# Transmitter_Rev_1.net
KiCad netlist of a schematic drawn in EAGLE
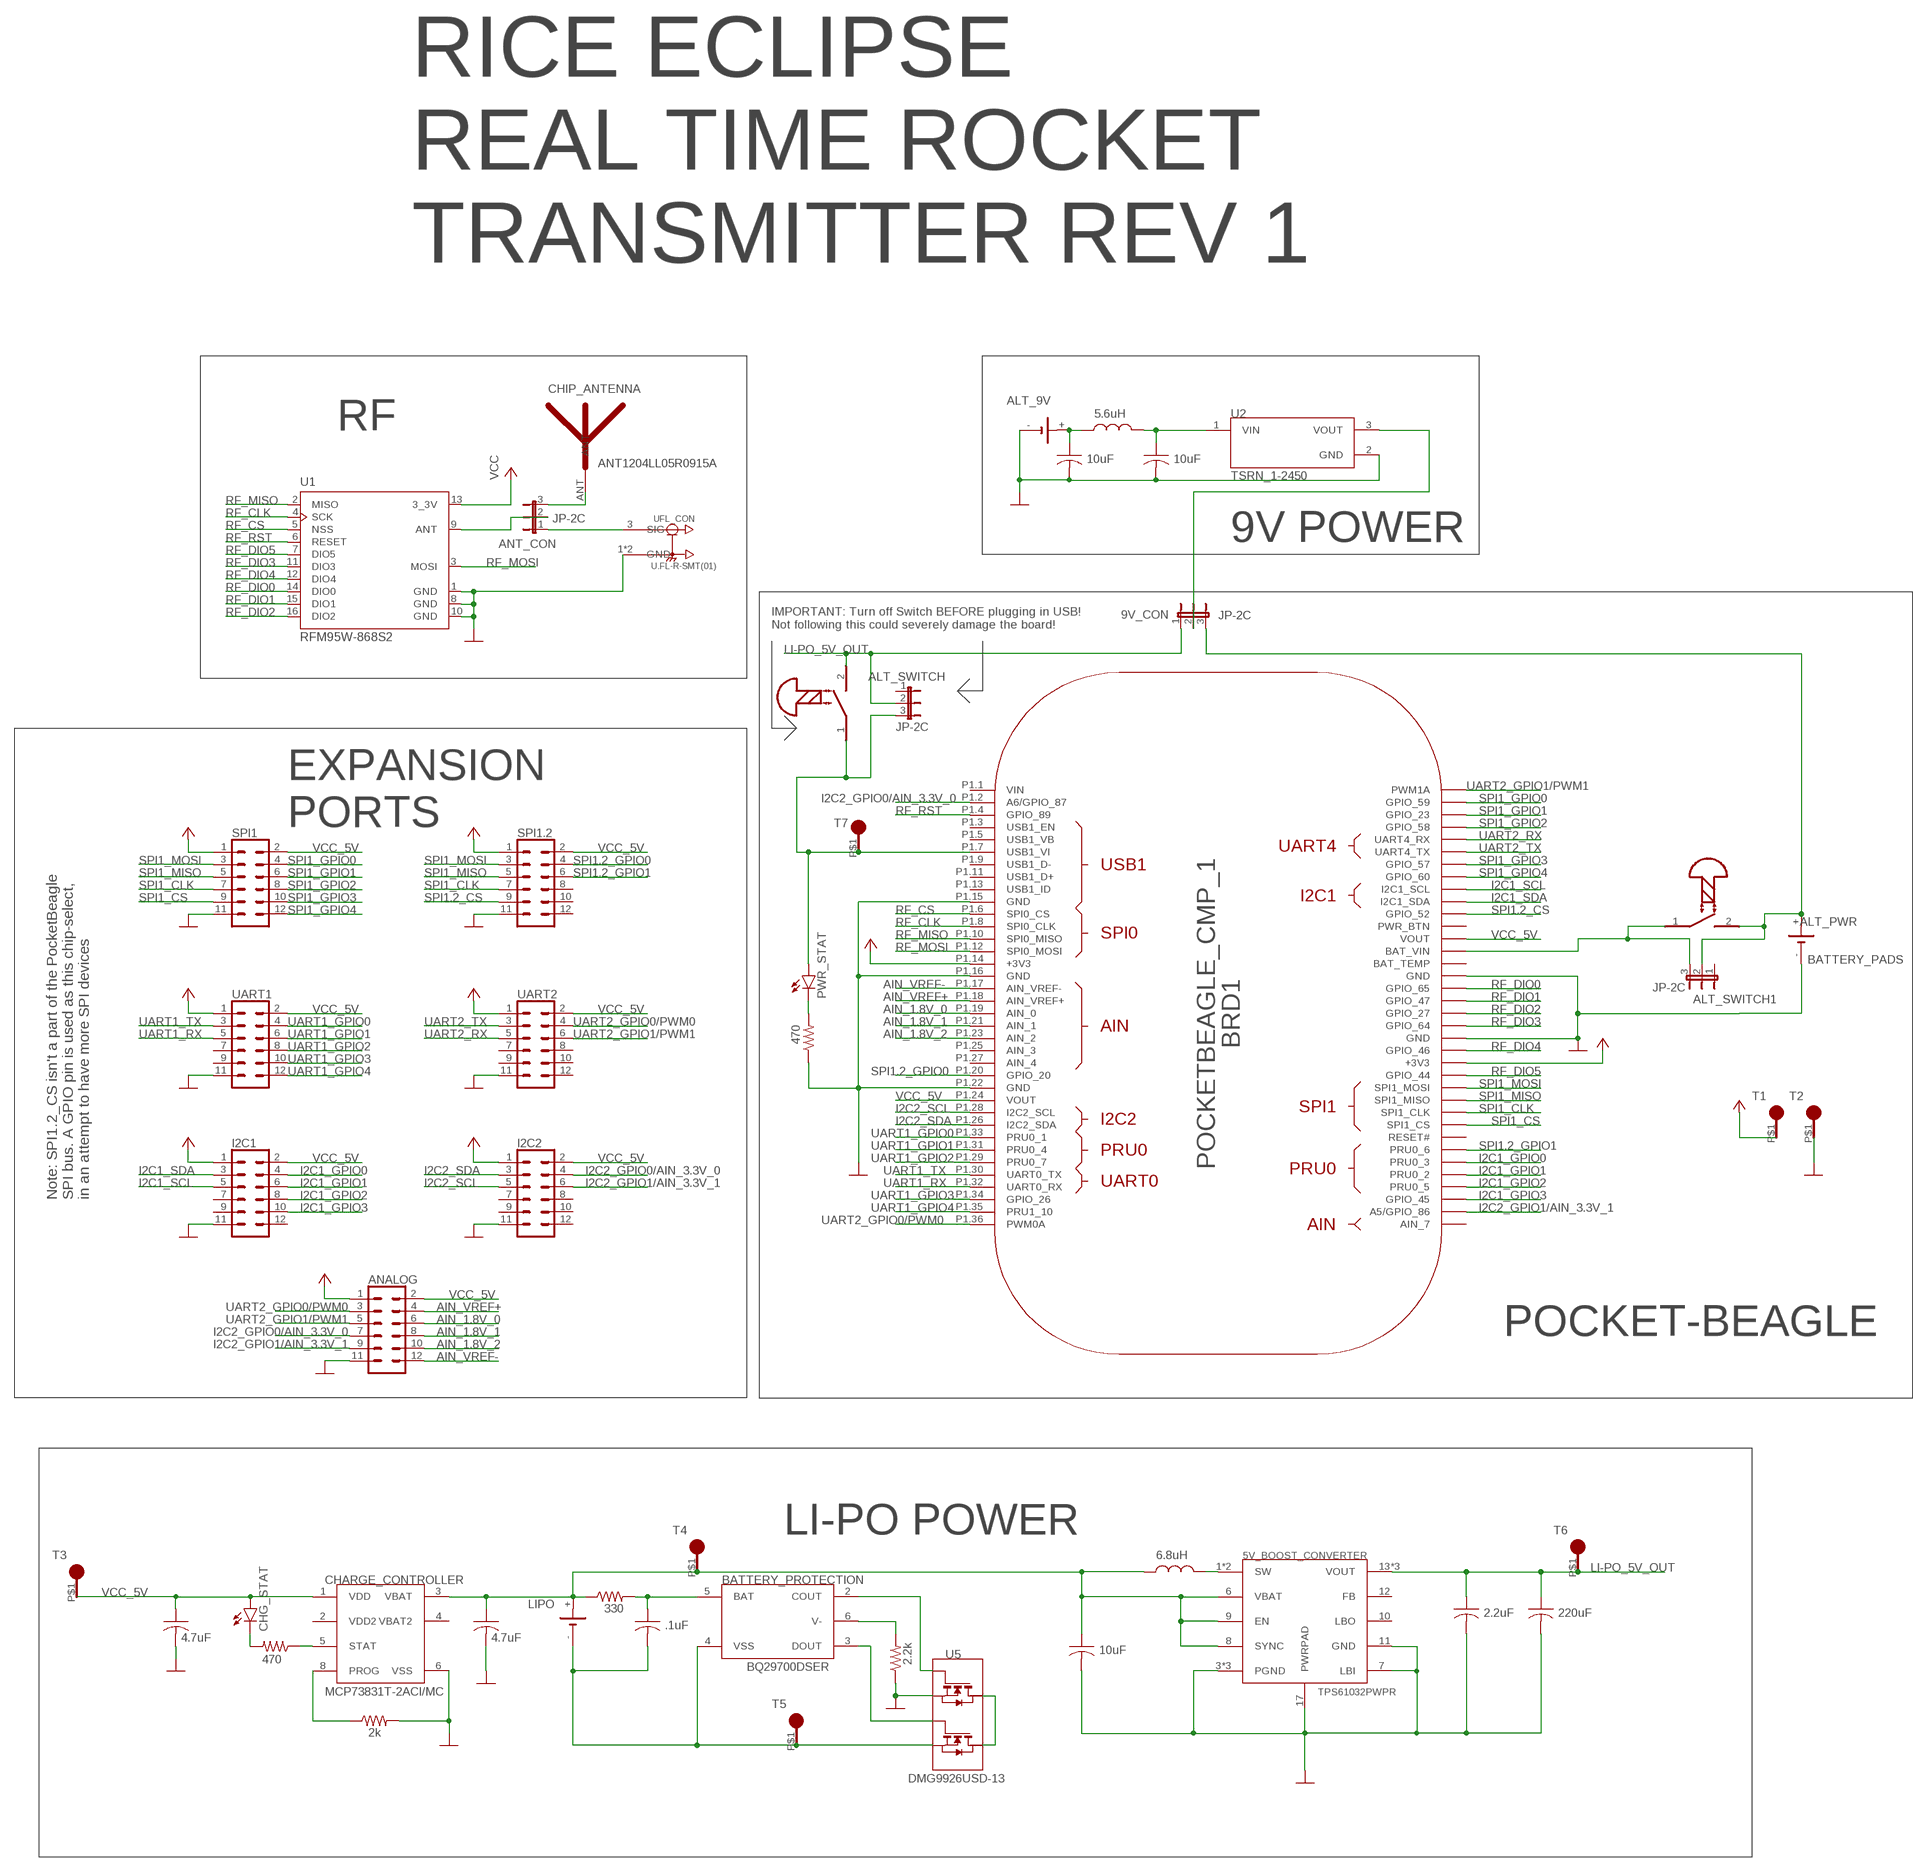
[diagram p0: schematic, sheet 1]

(export (version "E")
  (design (tool "Eeschema 10.0.6"))
  (components
    (comp (ref "5V_BOOST_CONVERTER")
      (value "TPS61032PWPR")
      (footprint "eagle-import:SOP65P640X110-17N")
      (fields (field (name "F") "TPS61032PWPR"))
      (libsource (lib "eagle-import") (part "TPS61032PWPR"))
    )
    (comp (ref "9V_C1")
      (value "10uF")
      (footprint "eagle-import:C1206")
      (libsource (lib "eagle-import") (part "C-SMD"))
    )
    (comp (ref "9V_C2")
      (value "10uF")
      (footprint "eagle-import:C1206")
      (libsource (lib "eagle-import") (part "C-SMD"))
    )
    (comp (ref "9V_CON")
      (value "JP-2C")
      (footprint "eagle-import:JP2")
      (libsource (lib "eagle-import") (part "JP-2C"))
    )
    (comp (ref "ALT_9V")
      (value "BATTERY_PADS")
      (footprint "eagle-import:POWER_PADS")
      (libsource (lib "eagle-import") (part "BATTERY_PADS"))
    )
    (comp (ref "ALT_PWR")
      (value "BATTERY_PADS")
      (footprint "eagle-import:POWER_PADS")
      (libsource (lib "eagle-import") (part "BATTERY_PADS"))
    )
    (comp (ref "ALT_SWITCH")
      (value "JP-2C")
      (footprint "eagle-import:JP2")
      (libsource (lib "eagle-import") (part "JP-2C"))
    )
    (comp (ref "ALT_SWITCH1")
      (value "JP-2C")
      (footprint "eagle-import:JP2")
      (libsource (lib "eagle-import") (part "JP-2C"))
    )
    (comp (ref "ANALOG")
      (value "2X6 FEMALE")
      (footprint "eagle-import:2X6")
      (libsource (lib "eagle-import") (part "SENSOR_BREAKOUTPTH_FEMALE"))
    )
    (comp (ref "ANT_CON")
      (value "JP-2C")
      (footprint "eagle-import:JP2")
      (libsource (lib "eagle-import") (part "JP-2C"))
    )
    (comp (ref "BATTERY_PROTECTION")
      (value "BQ29700DSER")
      (footprint "eagle-import:SON50P150X150X80-6N")
      (libsource (lib "eagle-import") (part "BQ29700DSER"))
    )
    (comp (ref "BRD1")
      (value "POCKETBEAGLE_CMP_1")
      (footprint "eagle-import:POCKETBEAGLE_CMP")
      (libsource (lib "eagle-import") (part "POCKETBEAGLE_?_1CMP"))
    )
    (comp (ref "CHARGE_CONTROLLER")
      (value "MCP73831T-2ACI/MC")
      (footprint "eagle-import:SON50P200X300X100-9N")
      (libsource (lib "eagle-import") (part "MCP73831T-2ACI/MC"))
    )
    (comp (ref "CHG_C1")
      (value "4.7uF")
      (footprint "eagle-import:C1206")
      (libsource (lib "eagle-import") (part "C-SMD"))
    )
    (comp (ref "CHG_C2")
      (value "4.7uF")
      (footprint "eagle-import:C1206")
      (libsource (lib "eagle-import") (part "C-SMD"))
    )
    (comp (ref "CHG_C3")
      (value ".1uF")
      (footprint "eagle-import:C1206")
      (libsource (lib "eagle-import") (part "C-SMD"))
    )
    (comp (ref "CHG_C4")
      (value "10uF")
      (footprint "eagle-import:C1206")
      (libsource (lib "eagle-import") (part "C-SMD"))
    )
    (comp (ref "CHG_C5")
      (value "2.2uF")
      (footprint "eagle-import:C1206")
      (libsource (lib "eagle-import") (part "C-SMD"))
    )
    (comp (ref "CHG_C6")
      (value "220uF")
      (footprint "eagle-import:C1206")
      (libsource (lib "eagle-import") (part "C-SMD"))
    )
    (comp (ref "CHG_R1")
      (value "2k")
      (footprint "eagle-import:RES_SMW52R0JT")
      (libsource (lib "eagle-import") (part "R-SMD"))
    )
    (comp (ref "CHG_R2")
      (value "470")
      (footprint "eagle-import:RES_SMW52R0JT")
      (libsource (lib "eagle-import") (part "R-SMD"))
    )
    (comp (ref "CHG_R3")
      (value "330")
      (footprint "eagle-import:RES_SMW52R0JT")
      (libsource (lib "eagle-import") (part "R-SMD"))
    )
    (comp (ref "CHG_R4")
      (value "2.2k")
      (footprint "eagle-import:RES_SMW52R0JT")
      (libsource (lib "eagle-import") (part "R-SMD"))
    )
    (comp (ref "CHG_R5")
      (value "470")
      (footprint "eagle-import:RES_SMW52R0JT")
      (libsource (lib "eagle-import") (part "R-SMD"))
    )
    (comp (ref "CHG_STAT")
      (value "LED5MM")
      (footprint "eagle-import:LED5MM")
      (libsource (lib "eagle-import") (part "LED5MM"))
    )
    (comp (ref "CHIP_ANTENNA")
      (value "ANT1204LL05R0915A")
      (footprint "eagle-import:SMD_ANTENNA")
      (libsource (lib "eagle-import") (part "ANT1204LL05R0915A"))
    )
    (comp (ref "I2C1")
      (value "2X6 FEMALE")
      (footprint "eagle-import:2X6")
      (libsource (lib "eagle-import") (part "SENSOR_BREAKOUTPTH_FEMALE"))
    )
    (comp (ref "I2C2")
      (value "2X6 FEMALE")
      (footprint "eagle-import:2X6")
      (libsource (lib "eagle-import") (part "SENSOR_BREAKOUTPTH_FEMALE"))
    )
    (comp (ref "L1")
      (value "5.6uH")
      (footprint "eagle-import:L-DS75LC")
      (libsource (lib "eagle-import") (part "L_SMD"))
    )
    (comp (ref "L2")
      (value "6.8uH")
      (footprint "eagle-import:L-DS75LC")
      (libsource (lib "eagle-import") (part "L_SMD"))
    )
    (comp (ref "LIPO")
      (value "BATTERY_PADS")
      (footprint "eagle-import:POWER_PADS")
      (libsource (lib "eagle-import") (part "BATTERY_PADS"))
    )
    (comp (ref "PWR_STAT")
      (value "LED5MM")
      (footprint "eagle-import:LED5MM")
      (libsource (lib "eagle-import") (part "LED5MM"))
    )
    (comp (ref "SPI1")
      (value "SNSR_BRKOUT")
      (footprint "eagle-import:2X6")
      (libsource (lib "eagle-import") (part "SENSOR_BREAKOUTPTH_FEMALE"))
    )
    (comp (ref "SPI1.2")
      (value "2X6 FEMALE")
      (footprint "eagle-import:2X6")
      (libsource (lib "eagle-import") (part "SENSOR_BREAKOUTPTH_FEMALE"))
    )
    (comp (ref "SW1")
      (value "SCREW_SWITCH")
      (footprint "eagle-import:SCREW_SWITCH")
      (libsource (lib "eagle-import") (part "SCREW_SWITCH"))
    )
    (comp (ref "SW2")
      (value "SCREW_SWITCH")
      (footprint "eagle-import:SCREW_SWITCH")
      (libsource (lib "eagle-import") (part "SCREW_SWITCH"))
    )
    (comp (ref "T1")
      (value "TEST_PAD")
      (footprint "eagle-import:TEST_PAD")
      (libsource (lib "eagle-import") (part "TEST_PAD"))
    )
    (comp (ref "T2")
      (value "TEST_PAD")
      (footprint "eagle-import:TEST_PAD")
      (libsource (lib "eagle-import") (part "TEST_PAD"))
    )
    (comp (ref "T3")
      (value "TEST_PAD")
      (footprint "eagle-import:TEST_PAD")
      (libsource (lib "eagle-import") (part "TEST_PAD"))
    )
    (comp (ref "T4")
      (value "TEST_PAD")
      (footprint "eagle-import:TEST_PAD")
      (libsource (lib "eagle-import") (part "TEST_PAD"))
    )
    (comp (ref "T5")
      (value "TEST_PAD")
      (footprint "eagle-import:TEST_PAD")
      (libsource (lib "eagle-import") (part "TEST_PAD"))
    )
    (comp (ref "T6")
      (value "TEST_PAD")
      (footprint "eagle-import:TEST_PAD")
      (libsource (lib "eagle-import") (part "TEST_PAD"))
    )
    (comp (ref "T7")
      (value "TEST_PAD")
      (footprint "eagle-import:TEST_PAD")
      (libsource (lib "eagle-import") (part "TEST_PAD"))
    )
    (comp (ref "U1")
      (value "RFM95W-868S2")
      (footprint "eagle-import:XCVR_RFM95W-868S2")
      (fields (field (name "MF") "RF"))
      (libsource (lib "eagle-import") (part "RFM95W-868S2"))
    )
    (comp (ref "U2")
      (value "TSRN_1-2450")
      (footprint "eagle-import:CONV_TSRN_1-2433")
      (fields (field (name "MF") "Traco Power") (field (name "MP") "TSRN 1-2450"))
      (libsource (lib "eagle-import") (part "TSRN_1-2450"))
    )
    (comp (ref "U5")
      (value "DMG9926USD-13")
      (footprint "eagle-import:SOIC127P600X175-8N")
      (libsource (lib "eagle-import") (part "DMG9926USD-13"))
    )
    (comp (ref "UART1")
      (value "2X6 FEMALE")
      (footprint "eagle-import:2X6")
      (libsource (lib "eagle-import") (part "SENSOR_BREAKOUTPTH_FEMALE"))
    )
    (comp (ref "UART2")
      (value "2X6 FEMALE")
      (footprint "eagle-import:2X6")
      (libsource (lib "eagle-import") (part "SENSOR_BREAKOUTPTH_FEMALE"))
    )
    (comp (ref "UFL_CON")
      (value "U.FL-R-SMT(01)")
      (footprint "eagle-import:HRS_U.FL-R-SMT(01)")
      (fields
        (field (name "DIGI-KEY_PART_NUMBER") "H9161-ND")
        (field (name "MF") "Hirose")
        (field (name "MP") "U.FL-R-SMT_01_")
      )
      (libsource (lib "eagle-import") (part "U.FL-R-SMT(01)"))
    )
  )
  (nets
    (net (code "1") (name "/AIN_1.8V_0") (class "Default")
      (node (ref "ANALOG") (pin "6") (pinfunction "6_6") (pintype "passive"))
      (node (ref "BRD1") (pin "P1.19") (pinfunction "AIN_0_P1.19") (pintype "bidirectional"))
    )
    (net (code "2") (name "/AIN_1.8V_1") (class "Default")
      (node (ref "ANALOG") (pin "8") (pinfunction "8_8") (pintype "passive"))
      (node (ref "BRD1") (pin "P1.21") (pinfunction "AIN_1_P1.21") (pintype "bidirectional"))
    )
    (net (code "3") (name "/AIN_1.8V_2") (class "Default")
      (node (ref "ANALOG") (pin "10") (pinfunction "10_10") (pintype "passive"))
      (node (ref "BRD1") (pin "P1.23") (pinfunction "AIN_2_P1.23") (pintype "bidirectional"))
    )
    (net (code "4") (name "/AIN_VREF+") (class "Default")
      (node (ref "ANALOG") (pin "4") (pinfunction "4_4") (pintype "passive"))
      (node (ref "BRD1") (pin "P1.18") (pinfunction "AIN_VREF+_P1.18") (pintype "bidirectional"))
    )
    (net (code "5") (name "/AIN_VREF-") (class "Default")
      (node (ref "ANALOG") (pin "12") (pinfunction "12_12") (pintype "passive"))
      (node (ref "BRD1") (pin "P1.17") (pinfunction "AIN_VREF-_P1.17") (pintype "bidirectional"))
    )
    (net (code "6") (name "/I2C1_GPIO0") (class "Default")
      (node (ref "BRD1") (pin "P2.30") (pinfunction "PRU0_3_P2.30") (pintype "bidirectional"))
      (node (ref "I2C1") (pin "4") (pinfunction "4_4") (pintype "passive"))
    )
    (net (code "7") (name "/I2C1_GPIO1") (class "Default")
      (node (ref "BRD1") (pin "P2.32") (pinfunction "PRU0_2_P2.32") (pintype "bidirectional"))
      (node (ref "I2C1") (pin "6") (pinfunction "6_6") (pintype "passive"))
    )
    (net (code "8") (name "/I2C1_GPIO2") (class "Default")
      (node (ref "BRD1") (pin "P2.34") (pinfunction "PRU0_5_P2.34") (pintype "bidirectional"))
      (node (ref "I2C1") (pin "8") (pinfunction "8_8") (pintype "passive"))
    )
    (net (code "9") (name "/I2C1_GPIO3") (class "Default")
      (node (ref "BRD1") (pin "P2.33") (pinfunction "GPIO_45_P2.33") (pintype "bidirectional"))
      (node (ref "I2C1") (pin "10") (pinfunction "10_10") (pintype "passive"))
    )
    (net (code "10") (name "/I2C1_SCL") (class "Default")
      (node (ref "BRD1") (pin "P2.9") (pinfunction "I2C1_SCL_P2.9") (pintype "bidirectional"))
      (node (ref "I2C1") (pin "5") (pinfunction "5_5") (pintype "passive"))
    )
    (net (code "11") (name "/I2C1_SDA") (class "Default")
      (node (ref "BRD1") (pin "P2.11") (pinfunction "I2C1_SDA_P2.11") (pintype "bidirectional"))
      (node (ref "I2C1") (pin "3") (pinfunction "3_3") (pintype "passive"))
    )
    (net (code "12") (name "/I2C2_GPIO0{slash}AIN_3.3V_0") (class "Default")
      (node (ref "ANALOG") (pin "7") (pinfunction "7_7") (pintype "passive"))
      (node (ref "BRD1") (pin "P1.2") (pinfunction "A6/GPIO_87_P1.2") (pintype "bidirectional"))
      (node (ref "I2C2") (pin "4") (pinfunction "4_4") (pintype "passive"))
    )
    (net (code "13") (name "/I2C2_GPIO1{slash}AIN_3.3V_1") (class "Default")
      (node (ref "ANALOG") (pin "9") (pinfunction "9_9") (pintype "passive"))
      (node (ref "BRD1") (pin "P2.35") (pinfunction "A5/GPIO_86_P2.35") (pintype "bidirectional"))
      (node (ref "I2C2") (pin "6") (pinfunction "6_6") (pintype "passive"))
    )
    (net (code "14") (name "/I2C2_SCL") (class "Default")
      (node (ref "BRD1") (pin "P1.28") (pinfunction "I2C2_SCL_P1.28") (pintype "bidirectional"))
      (node (ref "I2C2") (pin "5") (pinfunction "5_5") (pintype "passive"))
    )
    (net (code "15") (name "/I2C2_SDA") (class "Default")
      (node (ref "BRD1") (pin "P1.26") (pinfunction "I2C2_SDA_P1.26") (pintype "bidirectional"))
      (node (ref "I2C2") (pin "3") (pinfunction "3_3") (pintype "passive"))
    )
    (net (code "16") (name "/LI-PO_5V_OUT") (class "Default")
      (node (ref "5V_BOOST_CONVERTER") (pin "13") (pinfunction "VOUT_13") (pintype "bidirectional"))
      (node (ref "5V_BOOST_CONVERTER") (pin "14") (pinfunction "VOUT_14") (pintype "bidirectional"))
      (node (ref "5V_BOOST_CONVERTER") (pin "15") (pinfunction "VOUT_15") (pintype "bidirectional"))
      (node (ref "9V_CON") (pin "1") (pinfunction "1_1") (pintype "passive"))
      (node (ref "ALT_SWITCH") (pin "2") (pinfunction "2_2") (pintype "passive"))
      (node (ref "CHG_C5") (pin "1") (pinfunction "1_1") (pintype "passive"))
      (node (ref "CHG_C6") (pin "1") (pinfunction "1_1") (pintype "passive"))
      (node (ref "SW1") (pin "2") (pinfunction "2_2") (pintype "passive"))
      (node (ref "T6") (pin "P$1") (pinfunction "P$1_P$1") (pintype "passive"))
    )
    (net (code "17") (name "/RF_CLK") (class "Default")
      (node (ref "BRD1") (pin "P1.8") (pinfunction "SPI0_CLK_P1.8") (pintype "bidirectional"))
      (node (ref "U1") (pin "4") (pinfunction "SCK_4") (pintype "input"))
    )
    (net (code "18") (name "/RF_CS") (class "Default")
      (node (ref "BRD1") (pin "P1.6") (pinfunction "SPI0_CS_P1.6") (pintype "bidirectional"))
      (node (ref "U1") (pin "5") (pinfunction "NSS_5") (pintype "input"))
    )
    (net (code "19") (name "/RF_DIO0") (class "Default")
      (node (ref "BRD1") (pin "P2.17") (pinfunction "GPIO_65_P2.17") (pintype "bidirectional"))
      (node (ref "U1") (pin "14") (pinfunction "DIO0_14") (pintype "bidirectional"))
    )
    (net (code "20") (name "/RF_DIO1") (class "Default")
      (node (ref "BRD1") (pin "P2.18") (pinfunction "GPIO_47_P2.18") (pintype "bidirectional"))
      (node (ref "U1") (pin "15") (pinfunction "DIO1_15") (pintype "bidirectional"))
    )
    (net (code "21") (name "/RF_DIO2") (class "Default")
      (node (ref "BRD1") (pin "P2.19") (pinfunction "GPIO_27_P2.19") (pintype "bidirectional"))
      (node (ref "U1") (pin "16") (pinfunction "DIO2_16") (pintype "bidirectional"))
    )
    (net (code "22") (name "/RF_DIO3") (class "Default")
      (node (ref "BRD1") (pin "P2.20") (pinfunction "GPIO_64_P2.20") (pintype "bidirectional"))
      (node (ref "U1") (pin "11") (pinfunction "DIO3_11") (pintype "bidirectional"))
    )
    (net (code "23") (name "/RF_DIO4") (class "Default")
      (node (ref "BRD1") (pin "P2.22") (pinfunction "GPIO_46_P2.22") (pintype "bidirectional"))
      (node (ref "U1") (pin "12") (pinfunction "DIO4_12") (pintype "bidirectional"))
    )
    (net (code "24") (name "/RF_DIO5") (class "Default")
      (node (ref "BRD1") (pin "P2.24") (pinfunction "GPIO_44_P2.24") (pintype "bidirectional"))
      (node (ref "U1") (pin "7") (pinfunction "DIO5_7") (pintype "bidirectional"))
    )
    (net (code "25") (name "/RF_MISO") (class "Default")
      (node (ref "BRD1") (pin "P1.10") (pinfunction "SPI0_MISO_P1.10") (pintype "bidirectional"))
      (node (ref "U1") (pin "2") (pinfunction "MISO_2") (pintype "input"))
    )
    (net (code "26") (name "/RF_MOSI") (class "Default")
      (node (ref "BRD1") (pin "P1.12") (pinfunction "SPI0_MOSI_P1.12") (pintype "bidirectional"))
      (node (ref "U1") (pin "3") (pinfunction "MOSI_3") (pintype "output"))
    )
    (net (code "27") (name "/RF_RST") (class "Default")
      (node (ref "BRD1") (pin "P1.4") (pinfunction "GPIO_89_P1.4") (pintype "bidirectional"))
      (node (ref "U1") (pin "6") (pinfunction "RESET_6") (pintype "bidirectional"))
    )
    (net (code "28") (name "/SPI1.2_CS") (class "Default")
      (node (ref "BRD1") (pin "P2.10") (pinfunction "GPIO_52_P2.10") (pintype "bidirectional"))
      (node (ref "SPI1.2") (pin "9") (pinfunction "9_9") (pintype "passive"))
    )
    (net (code "29") (name "/SPI1.2_GPIO0") (class "Default")
      (node (ref "BRD1") (pin "P1.20") (pinfunction "GPIO_20_P1.20") (pintype "bidirectional"))
      (node (ref "SPI1.2") (pin "4") (pinfunction "4_4") (pintype "passive"))
    )
    (net (code "30") (name "/SPI1.2_GPIO1") (class "Default")
      (node (ref "BRD1") (pin "P2.28") (pinfunction "PRU0_6_P2.28") (pintype "bidirectional"))
      (node (ref "SPI1.2") (pin "6") (pinfunction "6_6") (pintype "passive"))
    )
    (net (code "31") (name "/SPI1_CLK") (class "Default")
      (node (ref "BRD1") (pin "P2.29") (pinfunction "SPI1_CLK_P2.29") (pintype "bidirectional"))
      (node (ref "SPI1") (pin "7") (pinfunction "7_7") (pintype "passive"))
      (node (ref "SPI1.2") (pin "7") (pinfunction "7_7") (pintype "passive"))
    )
    (net (code "32") (name "/SPI1_CS") (class "Default")
      (node (ref "BRD1") (pin "P2.31") (pinfunction "SPI1_CS_P2.31") (pintype "bidirectional"))
      (node (ref "SPI1") (pin "9") (pinfunction "9_9") (pintype "passive"))
    )
    (net (code "33") (name "/SPI1_GPIO0") (class "Default")
      (node (ref "BRD1") (pin "P2.2") (pinfunction "GPIO_59_P2.2") (pintype "bidirectional"))
      (node (ref "SPI1") (pin "4") (pinfunction "4_4") (pintype "passive"))
    )
    (net (code "34") (name "/SPI1_GPIO1") (class "Default")
      (node (ref "BRD1") (pin "P2.3") (pinfunction "GPIO_23_P2.3") (pintype "bidirectional"))
      (node (ref "SPI1") (pin "6") (pinfunction "6_6") (pintype "passive"))
    )
    (net (code "35") (name "/SPI1_GPIO2") (class "Default")
      (node (ref "BRD1") (pin "P2.4") (pinfunction "GPIO_58_P2.4") (pintype "bidirectional"))
      (node (ref "SPI1") (pin "8") (pinfunction "8_8") (pintype "passive"))
    )
    (net (code "36") (name "/SPI1_GPIO3") (class "Default")
      (node (ref "BRD1") (pin "P2.6") (pinfunction "GPIO_57_P2.6") (pintype "bidirectional"))
      (node (ref "SPI1") (pin "10") (pinfunction "10_10") (pintype "passive"))
    )
    (net (code "37") (name "/SPI1_GPIO4") (class "Default")
      (node (ref "BRD1") (pin "P2.8") (pinfunction "GPIO_60_P2.8") (pintype "bidirectional"))
      (node (ref "SPI1") (pin "12") (pinfunction "12_12") (pintype "passive"))
    )
    (net (code "38") (name "/SPI1_MISO") (class "Default")
      (node (ref "BRD1") (pin "P2.27") (pinfunction "SPI1_MISO_P2.27") (pintype "bidirectional"))
      (node (ref "SPI1") (pin "5") (pinfunction "5_5") (pintype "passive"))
      (node (ref "SPI1.2") (pin "5") (pinfunction "5_5") (pintype "passive"))
    )
    (net (code "39") (name "/SPI1_MOSI") (class "Default")
      (node (ref "BRD1") (pin "P2.25") (pinfunction "SPI1_MOSI_P2.25") (pintype "bidirectional"))
      (node (ref "SPI1") (pin "3") (pinfunction "3_3") (pintype "passive"))
      (node (ref "SPI1.2") (pin "3") (pinfunction "3_3") (pintype "passive"))
    )
    (net (code "40") (name "/UART1_GPIO0") (class "Default")
      (node (ref "BRD1") (pin "P1.33") (pinfunction "PRU0_1_P1.33") (pintype "bidirectional"))
      (node (ref "UART1") (pin "4") (pinfunction "4_4") (pintype "passive"))
    )
    (net (code "41") (name "/UART1_GPIO1") (class "Default")
      (node (ref "BRD1") (pin "P1.31") (pinfunction "PRU0_4_P1.31") (pintype "bidirectional"))
      (node (ref "UART1") (pin "6") (pinfunction "6_6") (pintype "passive"))
    )
    (net (code "42") (name "/UART1_GPIO2") (class "Default")
      (node (ref "BRD1") (pin "P1.29") (pinfunction "PRU0_7_P1.29") (pintype "bidirectional"))
      (node (ref "UART1") (pin "8") (pinfunction "8_8") (pintype "passive"))
    )
    (net (code "43") (name "/UART1_GPIO3") (class "Default")
      (node (ref "BRD1") (pin "P1.34") (pinfunction "GPIO_26_P1.34") (pintype "bidirectional"))
      (node (ref "UART1") (pin "10") (pinfunction "10_10") (pintype "passive"))
    )
    (net (code "44") (name "/UART1_GPIO4") (class "Default")
      (node (ref "BRD1") (pin "P1.35") (pinfunction "PRU1_10_P1.35") (pintype "bidirectional"))
      (node (ref "UART1") (pin "12") (pinfunction "12_12") (pintype "passive"))
    )
    (net (code "45") (name "/UART1_RX") (class "Default")
      (node (ref "BRD1") (pin "P1.32") (pinfunction "UART0_RX_P1.32") (pintype "bidirectional"))
      (node (ref "UART1") (pin "5") (pinfunction "5_5") (pintype "passive"))
    )
    (net (code "46") (name "/UART1_TX") (class "Default")
      (node (ref "BRD1") (pin "P1.30") (pinfunction "UART0_TX_P1.30") (pintype "bidirectional"))
      (node (ref "UART1") (pin "3") (pinfunction "3_3") (pintype "passive"))
    )
    (net (code "47") (name "/UART2_GPIO0{slash}PWM0") (class "Default")
      (node (ref "ANALOG") (pin "3") (pinfunction "3_3") (pintype "passive"))
      (node (ref "BRD1") (pin "P1.36") (pinfunction "PWM0A_P1.36") (pintype "bidirectional"))
      (node (ref "UART2") (pin "4") (pinfunction "4_4") (pintype "passive"))
    )
    (net (code "48") (name "/UART2_GPIO1{slash}PWM1") (class "Default")
      (node (ref "ANALOG") (pin "5") (pinfunction "5_5") (pintype "passive"))
      (node (ref "BRD1") (pin "P2.1") (pinfunction "PWM1A_P2.1") (pintype "bidirectional"))
      (node (ref "UART2") (pin "6") (pinfunction "6_6") (pintype "passive"))
    )
    (net (code "49") (name "/UART2_RX") (class "Default")
      (node (ref "BRD1") (pin "P2.5") (pinfunction "UART4_RX_P2.5") (pintype "bidirectional"))
      (node (ref "UART2") (pin "5") (pinfunction "5_5") (pintype "passive"))
    )
    (net (code "50") (name "/UART2_TX") (class "Default")
      (node (ref "BRD1") (pin "P2.7") (pinfunction "UART4_TX_P2.7") (pintype "bidirectional"))
      (node (ref "UART2") (pin "3") (pinfunction "3_3") (pintype "passive"))
    )
    (net (code "51") (name "/VCC_5V") (class "Default")
      (node (ref "ANALOG") (pin "2") (pinfunction "2_2") (pintype "passive"))
      (node (ref "BRD1") (pin "P1.24") (pinfunction "VOUT_P1.24") (pintype "bidirectional"))
      (node (ref "BRD1") (pin "P2.13") (pinfunction "VOUT_P2.13") (pintype "bidirectional"))
      (node (ref "CHARGE_CONTROLLER") (pin "1") (pinfunction "VDD_1") (pintype "bidirectional"))
      (node (ref "CHG_C1") (pin "1") (pinfunction "1_1") (pintype "passive"))
      (node (ref "CHG_STAT") (pin "A") (pinfunction "A_A") (pintype "passive"))
      (node (ref "I2C1") (pin "2") (pinfunction "2_2") (pintype "passive"))
      (node (ref "I2C2") (pin "2") (pinfunction "2_2") (pintype "passive"))
      (node (ref "SPI1") (pin "2") (pinfunction "2_2") (pintype "passive"))
      (node (ref "SPI1.2") (pin "2") (pinfunction "2_2") (pintype "passive"))
      (node (ref "T3") (pin "P$1") (pinfunction "P$1_P$1") (pintype "passive"))
      (node (ref "UART1") (pin "2") (pinfunction "2_2") (pintype "passive"))
      (node (ref "UART2") (pin "2") (pinfunction "2_2") (pintype "passive"))
    )
    (net (code "52") (name "GND") (class "Default")
      (node (ref "5V_BOOST_CONVERTER") (pin "11") (pinfunction "GND_11") (pintype "bidirectional"))
      (node (ref "5V_BOOST_CONVERTER") (pin "17") (pinfunction "PWRPAD_17") (pintype "bidirectional"))
      (node (ref "5V_BOOST_CONVERTER") (pin "3") (pinfunction "PGND_3") (pintype "bidirectional"))
      (node (ref "5V_BOOST_CONVERTER") (pin "4") (pinfunction "PGND_4") (pintype "bidirectional"))
      (node (ref "5V_BOOST_CONVERTER") (pin "5") (pinfunction "PGND_5") (pintype "bidirectional"))
      (node (ref "5V_BOOST_CONVERTER") (pin "7") (pinfunction "LBI_7") (pintype "bidirectional"))
      (node (ref "9V_C1") (pin "2") (pinfunction "2_2") (pintype "passive"))
      (node (ref "9V_C2") (pin "2") (pinfunction "2_2") (pintype "passive"))
      (node (ref "ALT_9V") (pin "-") (pinfunction "-_-") (pintype "passive"))
      (node (ref "ALT_PWR") (pin "-") (pinfunction "-_-") (pintype "passive"))
      (node (ref "ANALOG") (pin "11") (pinfunction "11_11") (pintype "passive"))
      (node (ref "BRD1") (pin "P1.15") (pinfunction "GND_P1.15") (pintype "bidirectional"))
      (node (ref "BRD1") (pin "P1.16") (pinfunction "GND_P1.16") (pintype "bidirectional"))
      (node (ref "BRD1") (pin "P1.22") (pinfunction "GND_P1.22") (pintype "bidirectional"))
      (node (ref "BRD1") (pin "P2.15") (pinfunction "GND_P2.15") (pintype "bidirectional"))
      (node (ref "BRD1") (pin "P2.21") (pinfunction "GND_P2.21") (pintype "bidirectional"))
      (node (ref "CHARGE_CONTROLLER") (pin "6") (pinfunction "VSS_6") (pintype "bidirectional"))
      (node (ref "CHG_C1") (pin "2") (pinfunction "2_2") (pintype "passive"))
      (node (ref "CHG_C2") (pin "2") (pinfunction "2_2") (pintype "passive"))
      (node (ref "CHG_C4") (pin "2") (pinfunction "2_2") (pintype "passive"))
      (node (ref "CHG_C5") (pin "2") (pinfunction "2_2") (pintype "passive"))
      (node (ref "CHG_C6") (pin "2") (pinfunction "2_2") (pintype "passive"))
      (node (ref "CHG_R1") (pin "2") (pinfunction "2_2") (pintype "passive"))
      (node (ref "CHG_R4") (pin "1") (pinfunction "1_1") (pintype "passive"))
      (node (ref "CHG_R5") (pin "1") (pinfunction "1_1") (pintype "passive"))
      (node (ref "I2C1") (pin "11") (pinfunction "11_11") (pintype "passive"))
      (node (ref "I2C2") (pin "11") (pinfunction "11_11") (pintype "passive"))
      (node (ref "SPI1") (pin "11") (pinfunction "11_11") (pintype "passive"))
      (node (ref "SPI1.2") (pin "11") (pinfunction "11_11") (pintype "passive"))
      (node (ref "T2") (pin "P$1") (pinfunction "P$1_P$1") (pintype "passive"))
      (node (ref "U1") (pin "1") (pinfunction "GND_1") (pintype "power_in"))
      (node (ref "U1") (pin "10") (pinfunction "GND_10") (pintype "power_in"))
      (node (ref "U1") (pin "8") (pinfunction "GND_8") (pintype "power_in"))
      (node (ref "U2") (pin "2") (pinfunction "GND_2") (pintype "power_in"))
      (node (ref "U5") (pin "1") (pinfunction "S1_1") (pintype "passive"))
      (node (ref "UART1") (pin "11") (pinfunction "11_11") (pintype "passive"))
      (node (ref "UART2") (pin "11") (pinfunction "11_11") (pintype "passive"))
      (node (ref "UFL_CON") (pin "1") (pinfunction "GND_1") (pintype "passive"))
      (node (ref "UFL_CON") (pin "2") (pinfunction "GND_2") (pintype "passive"))
    )
    (net (code "53") (name "Net-(5V_BOOST_CONVERTER-EN)") (class "Default")
      (node (ref "5V_BOOST_CONVERTER") (pin "6") (pinfunction "VBAT_6") (pintype "bidirectional"))
      (node (ref "5V_BOOST_CONVERTER") (pin "8") (pinfunction "SYNC_8") (pintype "bidirectional"))
      (node (ref "5V_BOOST_CONVERTER") (pin "9") (pinfunction "EN_9") (pintype "bidirectional"))
      (node (ref "CHARGE_CONTROLLER") (pin "3") (pinfunction "VBAT_3") (pintype "bidirectional"))
      (node (ref "CHG_C2") (pin "1") (pinfunction "1_1") (pintype "passive"))
      (node (ref "CHG_C4") (pin "1") (pinfunction "1_1") (pintype "passive"))
      (node (ref "CHG_R3") (pin "1") (pinfunction "1_1") (pintype "passive"))
      (node (ref "L2") (pin "P$1") (pinfunction "1_P$1") (pintype "passive"))
      (node (ref "LIPO") (pin "+") (pinfunction "+_+") (pintype "passive"))
      (node (ref "T4") (pin "P$1") (pinfunction "P$1_P$1") (pintype "passive"))
    )
    (net (code "54") (name "Net-(9V_CON-Pad3)") (class "Default")
      (node (ref "9V_CON") (pin "3") (pinfunction "3_3") (pintype "passive"))
      (node (ref "ALT_PWR") (pin "+") (pinfunction "+_+") (pintype "passive"))
      (node (ref "ALT_SWITCH1") (pin "2") (pinfunction "2_2") (pintype "passive"))
      (node (ref "SW2") (pin "2") (pinfunction "2_2") (pintype "passive"))
    )
    (net (code "55") (name "Net-(ANT_CON-Pad3)") (class "Default")
      (node (ref "ANT_CON") (pin "3") (pinfunction "3_3") (pintype "passive"))
      (node (ref "CHIP_ANTENNA") (pin "ANT") (pinfunction "ANT_ANT") (pintype "bidirectional"))
    )
    (net (code "56") (name "Net-(BATTERY_PROTECTION-BAT)") (class "Default")
      (node (ref "BATTERY_PROTECTION") (pin "5") (pinfunction "BAT_5") (pintype "bidirectional"))
      (node (ref "CHG_C3") (pin "1") (pinfunction "1_1") (pintype "passive"))
      (node (ref "CHG_R3") (pin "2") (pinfunction "2_2") (pintype "passive"))
    )
    (net (code "57") (name "Net-(BATTERY_PROTECTION-COUT)") (class "Default")
      (node (ref "BATTERY_PROTECTION") (pin "2") (pinfunction "COUT_2") (pintype "bidirectional"))
      (node (ref "U5") (pin "2") (pinfunction "G1_2") (pintype "passive"))
    )
    (net (code "58") (name "Net-(BATTERY_PROTECTION-DOUT)") (class "Default")
      (node (ref "BATTERY_PROTECTION") (pin "3") (pinfunction "DOUT_3") (pintype "bidirectional"))
      (node (ref "U5") (pin "4") (pinfunction "G2_4") (pintype "passive"))
    )
    (net (code "59") (name "Net-(BATTERY_PROTECTION-V-)") (class "Default")
      (node (ref "BATTERY_PROTECTION") (pin "6") (pinfunction "V-_6") (pintype "bidirectional"))
      (node (ref "CHG_R4") (pin "2") (pinfunction "2_2") (pintype "passive"))
    )
    (net (code "60") (name "Net-(BATTERY_PROTECTION-VSS)") (class "Default")
      (node (ref "BATTERY_PROTECTION") (pin "4") (pinfunction "VSS_4") (pintype "bidirectional"))
      (node (ref "CHG_C3") (pin "2") (pinfunction "2_2") (pintype "passive"))
      (node (ref "LIPO") (pin "-") (pinfunction "-_-") (pintype "passive"))
      (node (ref "T5") (pin "P$1") (pinfunction "P$1_P$1") (pintype "passive"))
      (node (ref "U5") (pin "3") (pinfunction "S2_3") (pintype "passive"))
    )
    (net (code "61") (name "Net-(BRD1-BAT_VIN)") (class "Default")
      (node (ref "ALT_SWITCH1") (pin "3") (pinfunction "3_3") (pintype "passive"))
      (node (ref "BRD1") (pin "P2.14") (pinfunction "BAT_VIN_P2.14") (pintype "bidirectional"))
      (node (ref "SW2") (pin "1") (pinfunction "1_1") (pintype "passive"))
    )
    (net (code "62") (name "Net-(BRD1-USB1_VI)") (class "Default")
      (node (ref "ALT_SWITCH") (pin "3") (pinfunction "3_3") (pintype "passive"))
      (node (ref "BRD1") (pin "P1.7") (pinfunction "USB1_VI_P1.7") (pintype "bidirectional"))
      (node (ref "PWR_STAT") (pin "A") (pinfunction "A_A") (pintype "passive"))
      (node (ref "SW1") (pin "1") (pinfunction "1_1") (pintype "passive"))
      (node (ref "T7") (pin "P$1") (pinfunction "P$1_P$1") (pintype "passive"))
    )
    (net (code "63") (name "Net-(CHARGE_CONTROLLER-PROG)") (class "Default")
      (node (ref "CHARGE_CONTROLLER") (pin "8") (pinfunction "PROG_8") (pintype "bidirectional"))
      (node (ref "CHG_R1") (pin "1") (pinfunction "1_1") (pintype "passive"))
    )
    (net (code "64") (name "Net-(CHARGE_CONTROLLER-STAT)") (class "Default")
      (node (ref "CHARGE_CONTROLLER") (pin "5") (pinfunction "STAT_5") (pintype "bidirectional"))
      (node (ref "CHG_R2") (pin "1") (pinfunction "1_1") (pintype "passive"))
    )
    (net (code "65") (name "Net-(CHG_STAT-C)") (class "Default")
      (node (ref "CHG_R2") (pin "2") (pinfunction "2_2") (pintype "passive"))
      (node (ref "CHG_STAT") (pin "K") (pinfunction "C_K") (pintype "passive"))
    )
    (net (code "66") (name "Net-(L1-1)") (class "Default")
      (node (ref "9V_C1") (pin "1") (pinfunction "1_1") (pintype "passive"))
      (node (ref "ALT_9V") (pin "+") (pinfunction "+_+") (pintype "passive"))
      (node (ref "L1") (pin "P$1") (pinfunction "1_P$1") (pintype "passive"))
    )
    (net (code "67") (name "Net-(L1-2)") (class "Default")
      (node (ref "9V_C2") (pin "1") (pinfunction "1_1") (pintype "passive"))
      (node (ref "L1") (pin "P$2") (pinfunction "2_P$2") (pintype "passive"))
      (node (ref "U2") (pin "1") (pinfunction "VIN_1") (pintype "input"))
    )
    (net (code "68") (name "Net-(L2-2)") (class "Default")
      (node (ref "5V_BOOST_CONVERTER") (pin "1") (pinfunction "SW_1") (pintype "bidirectional"))
      (node (ref "5V_BOOST_CONVERTER") (pin "2") (pinfunction "SW_2") (pintype "bidirectional"))
      (node (ref "L2") (pin "P$2") (pinfunction "2_P$2") (pintype "passive"))
    )
    (net (code "69") (name "Net-(PWR_STAT-C)") (class "Default")
      (node (ref "CHG_R5") (pin "2") (pinfunction "2_2") (pintype "passive"))
      (node (ref "PWR_STAT") (pin "K") (pinfunction "C_K") (pintype "passive"))
    )
    (net (code "70") (name "Net-(U1-ANT)") (class "Default")
      (node (ref "ANT_CON") (pin "2") (pinfunction "2_2") (pintype "passive"))
      (node (ref "U1") (pin "9") (pinfunction "ANT_9") (pintype "passive"))
    )
    (net (code "71") (name "Net-(U2-VOUT)") (class "Default")
      (node (ref "9V_CON") (pin "2") (pinfunction "2_2") (pintype "passive"))
      (node (ref "U2") (pin "3") (pinfunction "VOUT_3") (pintype "output"))
    )
    (net (code "72") (name "Net-(U5-D1-Pad7)") (class "Default")
      (node (ref "U5") (pin "5") (pinfunction "D2_5") (pintype "passive"))
      (node (ref "U5") (pin "6") (pinfunction "D2_6") (pintype "passive"))
      (node (ref "U5") (pin "7") (pinfunction "D1_7") (pintype "passive"))
      (node (ref "U5") (pin "8") (pinfunction "D1_8") (pintype "passive"))
    )
    (net (code "73") (name "Net-(UFL_CON-SIG)") (class "Default")
      (node (ref "ANT_CON") (pin "1") (pinfunction "1_1") (pintype "passive"))
      (node (ref "UFL_CON") (pin "3") (pinfunction "SIG_3") (pintype "passive"))
    )
    (net (code "74") (name "VCC") (class "Default")
      (node (ref "ANALOG") (pin "1") (pinfunction "1_1") (pintype "passive"))
      (node (ref "BRD1") (pin "P1.14") (pinfunction "+3V3_P1.14") (pintype "bidirectional"))
      (node (ref "BRD1") (pin "P2.23") (pinfunction "+3V3_P2.23") (pintype "bidirectional"))
      (node (ref "I2C1") (pin "1") (pinfunction "1_1") (pintype "passive"))
      (node (ref "I2C2") (pin "1") (pinfunction "1_1") (pintype "passive"))
      (node (ref "SPI1") (pin "1") (pinfunction "1_1") (pintype "passive"))
      (node (ref "SPI1.2") (pin "1") (pinfunction "1_1") (pintype "passive"))
      (node (ref "T1") (pin "P$1") (pinfunction "P$1_P$1") (pintype "passive"))
      (node (ref "U1") (pin "13") (pinfunction "3_3V_13") (pintype "power_in"))
      (node (ref "UART1") (pin "1") (pinfunction "1_1") (pintype "passive"))
      (node (ref "UART2") (pin "1") (pinfunction "1_1") (pintype "passive"))
    )
    (net (code "75") (name "unconnected-(5V_BOOST_CONVERTER-FB-Pad12)") (class "Default")
      (node (ref "5V_BOOST_CONVERTER") (pin "12") (pinfunction "FB_12") (pintype "bidirectional"))
    )
    (net (code "76") (name "unconnected-(5V_BOOST_CONVERTER-LBO-Pad10)") (class "Default")
      (node (ref "5V_BOOST_CONVERTER") (pin "10") (pinfunction "LBO_10") (pintype "bidirectional"))
    )
    (net (code "77") (name "unconnected-(ALT_SWITCH-Pad1)") (class "Default")
      (node (ref "ALT_SWITCH") (pin "1") (pinfunction "1_1") (pintype "passive"))
    )
    (net (code "78") (name "unconnected-(ALT_SWITCH1-Pad1)") (class "Default")
      (node (ref "ALT_SWITCH1") (pin "1") (pinfunction "1_1") (pintype "passive"))
    )
    (net (code "79") (name "unconnected-(BRD1-AIN_3-PadP1.25)") (class "Default")
      (node (ref "BRD1") (pin "P1.25") (pinfunction "AIN_3_P1.25") (pintype "bidirectional"))
    )
    (net (code "80") (name "unconnected-(BRD1-AIN_4-PadP1.27)") (class "Default")
      (node (ref "BRD1") (pin "P1.27") (pinfunction "AIN_4_P1.27") (pintype "bidirectional"))
    )
    (net (code "81") (name "unconnected-(BRD1-AIN_7-PadP2.36)") (class "Default")
      (node (ref "BRD1") (pin "P2.36") (pinfunction "AIN_7_P2.36") (pintype "bidirectional"))
    )
    (net (code "82") (name "unconnected-(BRD1-BAT_TEMP-PadP2.16)") (class "Default")
      (node (ref "BRD1") (pin "P2.16") (pinfunction "BAT_TEMP_P2.16") (pintype "bidirectional"))
    )
    (net (code "83") (name "unconnected-(BRD1-PWR_BTN-PadP2.12)") (class "Default")
      (node (ref "BRD1") (pin "P2.12") (pinfunction "PWR_BTN_P2.12") (pintype "bidirectional"))
    )
    (net (code "84") (name "unconnected-(BRD1-RESET#-PadP2.26)") (class "Default")
      (node (ref "BRD1") (pin "P2.26") (pinfunction "RESET#_P2.26") (pintype "bidirectional"))
    )
    (net (code "85") (name "unconnected-(BRD1-USB1_D+-PadP1.11)") (class "Default")
      (node (ref "BRD1") (pin "P1.11") (pinfunction "USB1_D+_P1.11") (pintype "bidirectional"))
    )
    (net (code "86") (name "unconnected-(BRD1-USB1_D--PadP1.9)") (class "Default")
      (node (ref "BRD1") (pin "P1.9") (pinfunction "USB1_D-_P1.9") (pintype "bidirectional"))
    )
    (net (code "87") (name "unconnected-(BRD1-USB1_EN-PadP1.3)") (class "Default")
      (node (ref "BRD1") (pin "P1.3") (pinfunction "USB1_EN_P1.3") (pintype "bidirectional"))
    )
    (net (code "88") (name "unconnected-(BRD1-USB1_ID-PadP1.13)") (class "Default")
      (node (ref "BRD1") (pin "P1.13") (pinfunction "USB1_ID_P1.13") (pintype "bidirectional"))
    )
    (net (code "89") (name "unconnected-(BRD1-USB1_VB-PadP1.5)") (class "Default")
      (node (ref "BRD1") (pin "P1.5") (pinfunction "USB1_VB_P1.5") (pintype "bidirectional"))
    )
    (net (code "90") (name "unconnected-(BRD1-VIN-PadP1.1)") (class "Default")
      (node (ref "BRD1") (pin "P1.1") (pinfunction "VIN_P1.1") (pintype "bidirectional"))
    )
    (net (code "91") (name "unconnected-(CHARGE_CONTROLLER-VBAT2-Pad4)") (class "Default")
      (node (ref "CHARGE_CONTROLLER") (pin "4") (pinfunction "VBAT2_4") (pintype "bidirectional"))
    )
    (net (code "92") (name "unconnected-(CHARGE_CONTROLLER-VDD2-Pad2)") (class "Default")
      (node (ref "CHARGE_CONTROLLER") (pin "2") (pinfunction "VDD2_2") (pintype "bidirectional"))
    )
    (net (code "93") (name "unconnected-(I2C1-Pad7)") (class "Default")
      (node (ref "I2C1") (pin "7") (pinfunction "7_7") (pintype "passive"))
    )
    (net (code "94") (name "unconnected-(I2C1-Pad9)") (class "Default")
      (node (ref "I2C1") (pin "9") (pinfunction "9_9") (pintype "passive"))
    )
    (net (code "95") (name "unconnected-(I2C1-Pad12)") (class "Default")
      (node (ref "I2C1") (pin "12") (pinfunction "12_12") (pintype "passive"))
    )
    (net (code "96") (name "unconnected-(I2C2-Pad7)") (class "Default")
      (node (ref "I2C2") (pin "7") (pinfunction "7_7") (pintype "passive"))
    )
    (net (code "97") (name "unconnected-(I2C2-Pad8)") (class "Default")
      (node (ref "I2C2") (pin "8") (pinfunction "8_8") (pintype "passive"))
    )
    (net (code "98") (name "unconnected-(I2C2-Pad9)") (class "Default")
      (node (ref "I2C2") (pin "9") (pinfunction "9_9") (pintype "passive"))
    )
    (net (code "99") (name "unconnected-(I2C2-Pad10)") (class "Default")
      (node (ref "I2C2") (pin "10") (pinfunction "10_10") (pintype "passive"))
    )
    (net (code "100") (name "unconnected-(I2C2-Pad12)") (class "Default")
      (node (ref "I2C2") (pin "12") (pinfunction "12_12") (pintype "passive"))
    )
    (net (code "101") (name "unconnected-(SPI1.2-Pad8)") (class "Default")
      (node (ref "SPI1.2") (pin "8") (pinfunction "8_8") (pintype "passive"))
    )
    (net (code "102") (name "unconnected-(SPI1.2-Pad10)") (class "Default")
      (node (ref "SPI1.2") (pin "10") (pinfunction "10_10") (pintype "passive"))
    )
    (net (code "103") (name "unconnected-(SPI1.2-Pad12)") (class "Default")
      (node (ref "SPI1.2") (pin "12") (pinfunction "12_12") (pintype "passive"))
    )
    (net (code "104") (name "unconnected-(UART1-Pad7)") (class "Default")
      (node (ref "UART1") (pin "7") (pinfunction "7_7") (pintype "passive"))
    )
    (net (code "105") (name "unconnected-(UART1-Pad9)") (class "Default")
      (node (ref "UART1") (pin "9") (pinfunction "9_9") (pintype "passive"))
    )
    (net (code "106") (name "unconnected-(UART2-Pad7)") (class "Default")
      (node (ref "UART2") (pin "7") (pinfunction "7_7") (pintype "passive"))
    )
    (net (code "107") (name "unconnected-(UART2-Pad8)") (class "Default")
      (node (ref "UART2") (pin "8") (pinfunction "8_8") (pintype "passive"))
    )
    (net (code "108") (name "unconnected-(UART2-Pad9)") (class "Default")
      (node (ref "UART2") (pin "9") (pinfunction "9_9") (pintype "passive"))
    )
    (net (code "109") (name "unconnected-(UART2-Pad10)") (class "Default")
      (node (ref "UART2") (pin "10") (pinfunction "10_10") (pintype "passive"))
    )
    (net (code "110") (name "unconnected-(UART2-Pad12)") (class "Default")
      (node (ref "UART2") (pin "12") (pinfunction "12_12") (pintype "passive"))
    )
  )
)
